# TeensyAmp_R5_1.net
KiCad netlist of a schematic drawn in EAGLE
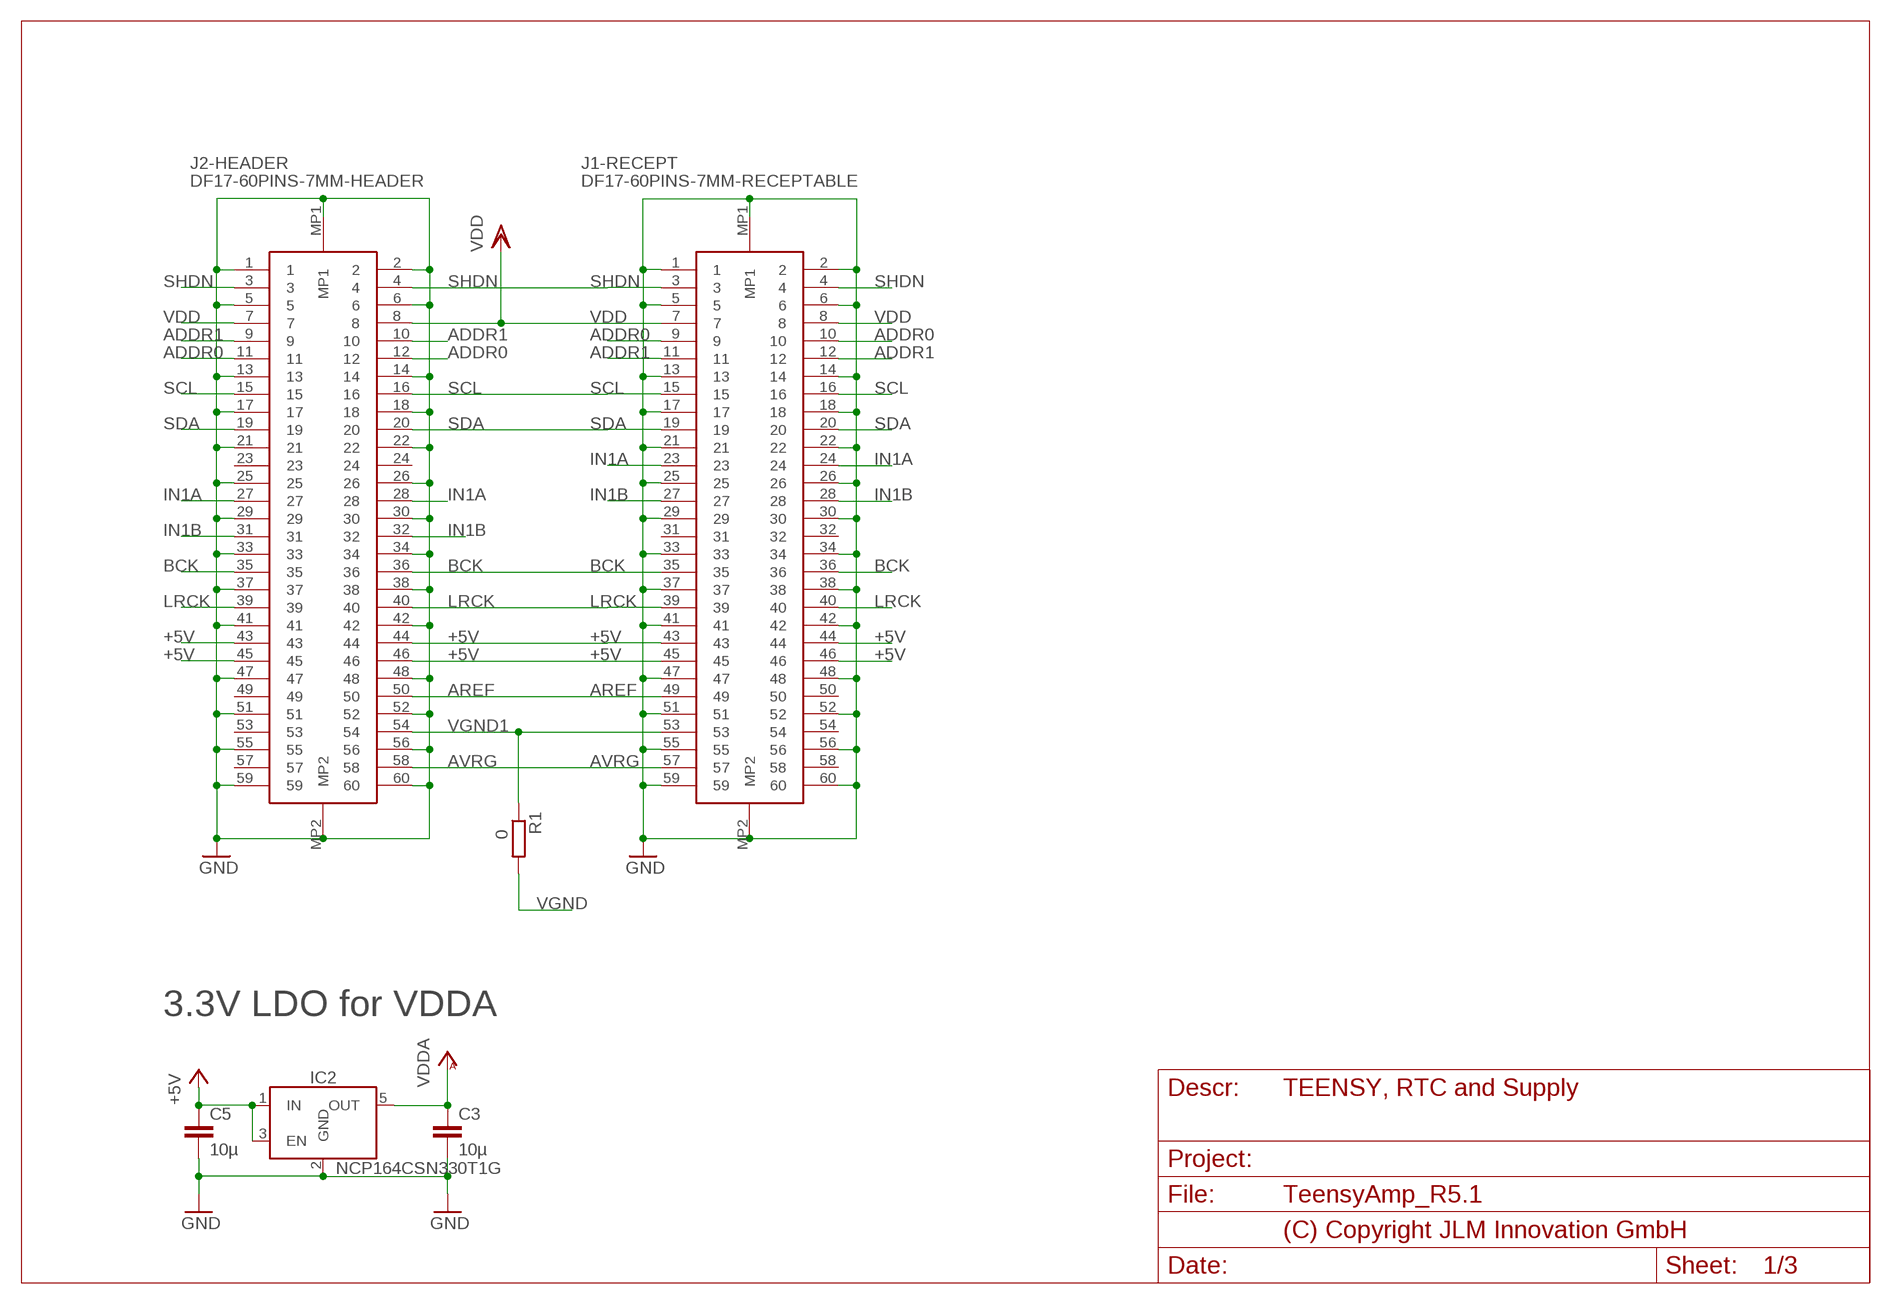
[diagram p0: schematic, sheet 1]
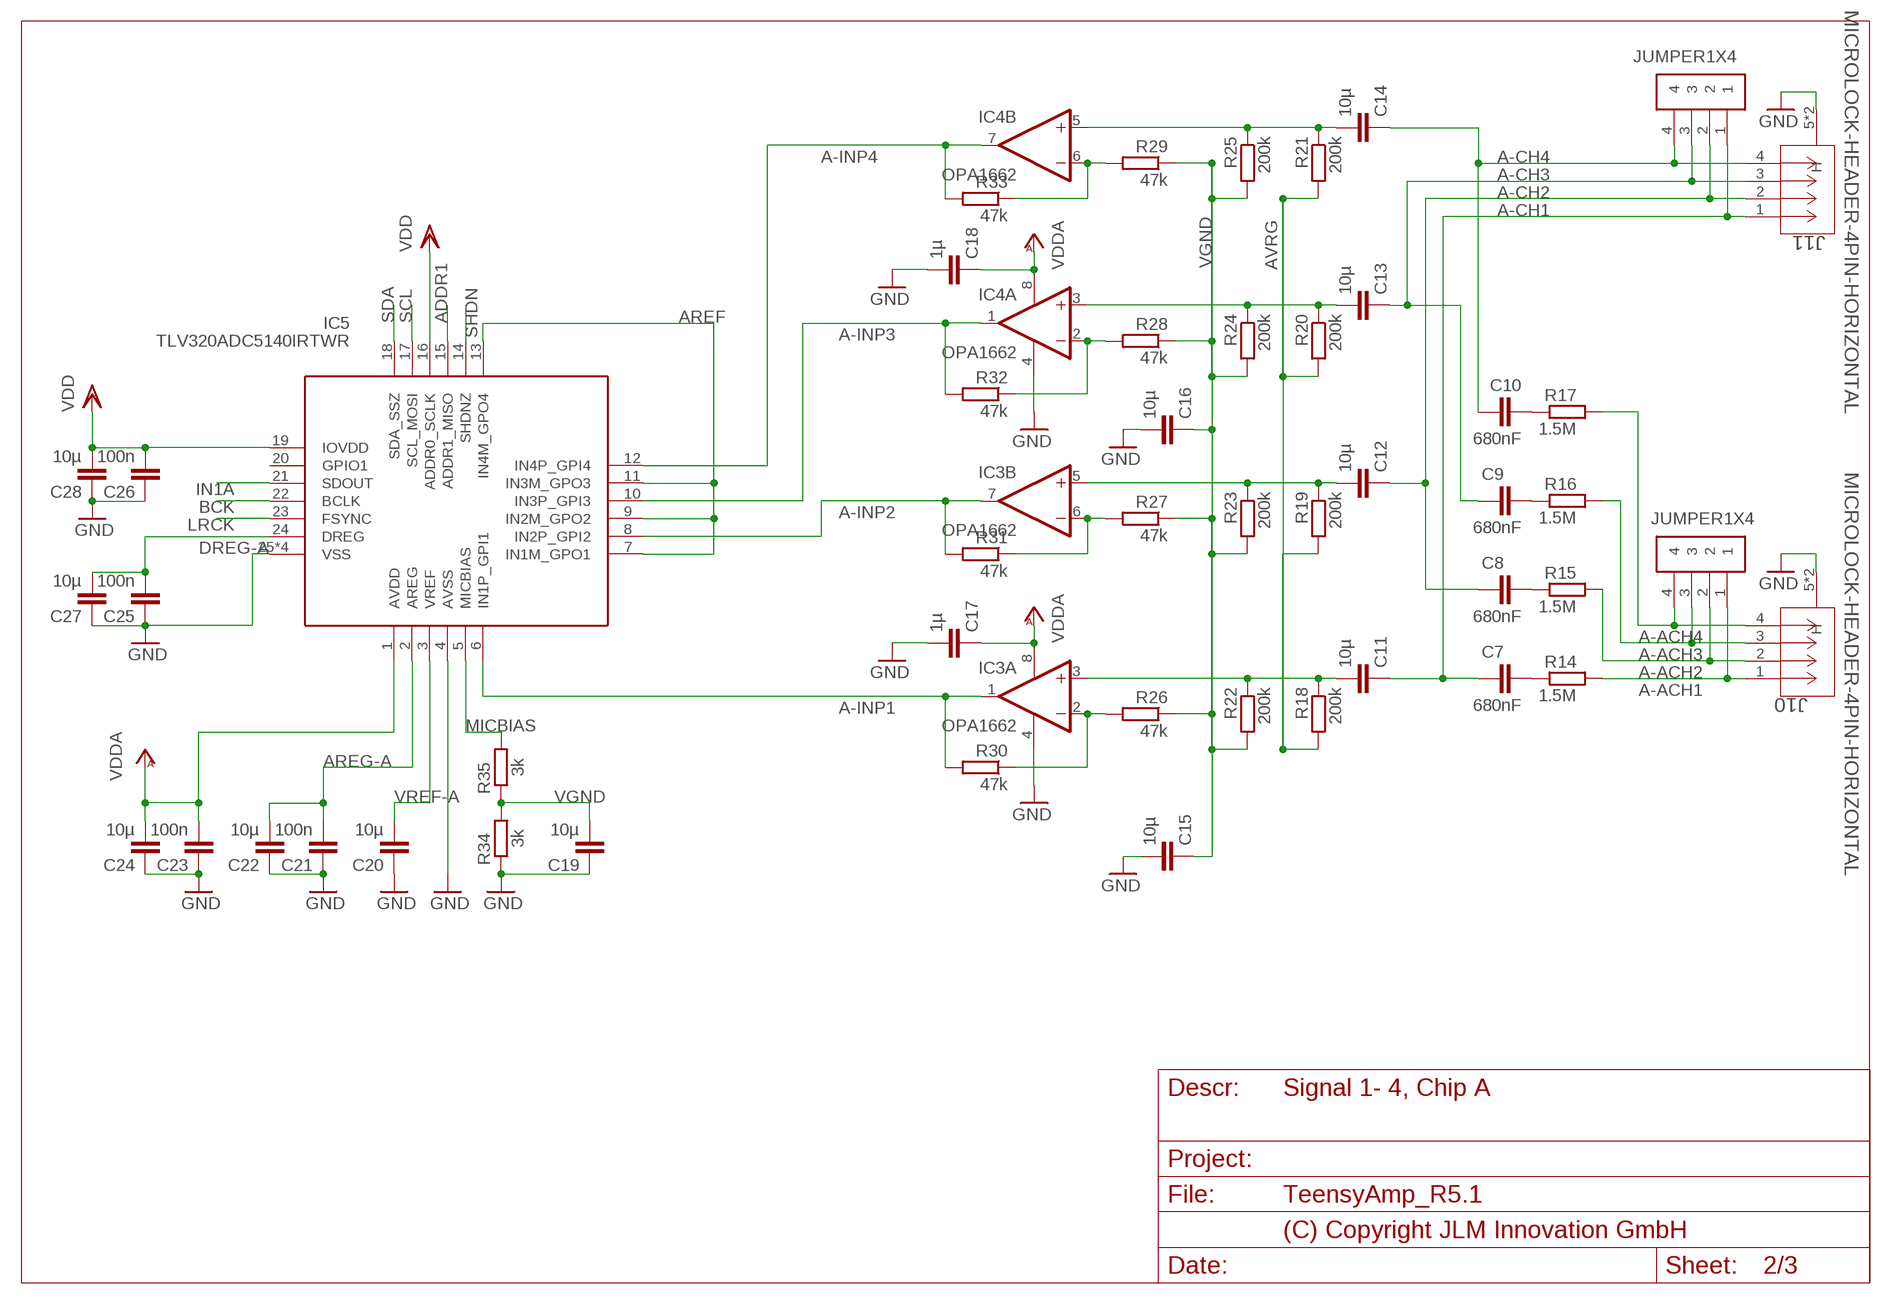
[diagram p1: schematic, sheet 2]
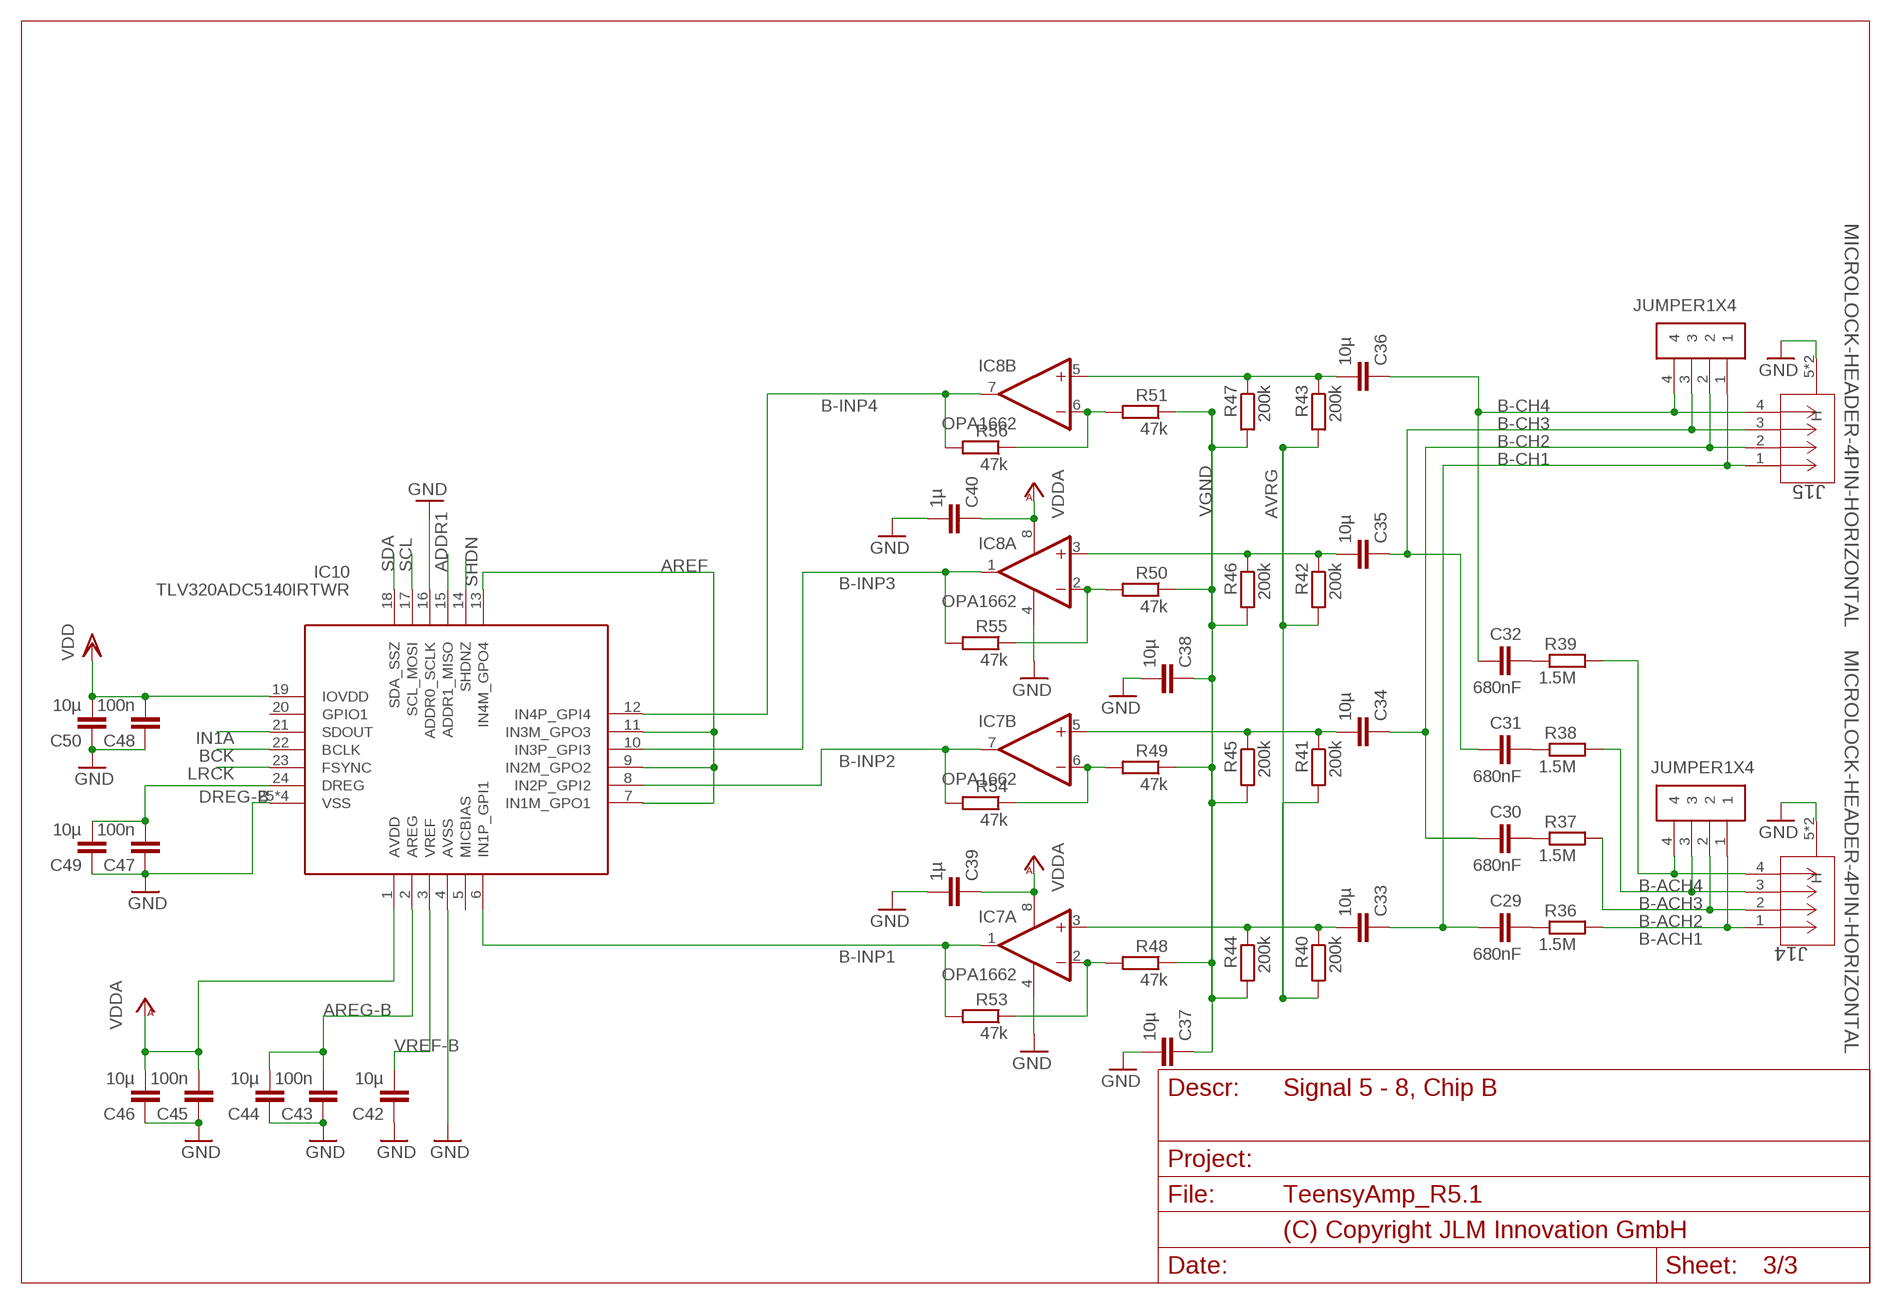
[diagram p2: schematic, sheet 3]

(export (version "E")
  (design (tool "Eeschema 10.0.6"))
  (components
    (comp (ref "C29")
      (value "680nF")
      (footprint "eagle-import:C0805")
      (libsource (lib "eagle-import") (part "C-EUC0805"))
    )
    (comp (ref "C30")
      (value "680nF")
      (footprint "eagle-import:C0805")
      (libsource (lib "eagle-import") (part "C-EUC0805"))
    )
    (comp (ref "C31")
      (value "680nF")
      (footprint "eagle-import:C0805")
      (libsource (lib "eagle-import") (part "C-EUC0805"))
    )
    (comp (ref "C32")
      (value "680nF")
      (footprint "eagle-import:C0805")
      (libsource (lib "eagle-import") (part "C-EUC0805"))
    )
    (comp (ref "C33")
      (value "10µ")
      (footprint "eagle-import:C0805")
      (libsource (lib "eagle-import") (part "C-EUC0805"))
    )
    (comp (ref "C34")
      (value "10µ")
      (footprint "eagle-import:C0805")
      (libsource (lib "eagle-import") (part "C-EUC0805"))
    )
    (comp (ref "C35")
      (value "10µ")
      (footprint "eagle-import:C0805")
      (libsource (lib "eagle-import") (part "C-EUC0805"))
    )
    (comp (ref "C36")
      (value "10µ")
      (footprint "eagle-import:C0805")
      (libsource (lib "eagle-import") (part "C-EUC0805"))
    )
    (comp (ref "C37")
      (value "10µ")
      (footprint "eagle-import:C0603")
      (libsource (lib "eagle-import") (part "C-EUC0603"))
    )
    (comp (ref "C38")
      (value "10µ")
      (footprint "eagle-import:C0603")
      (libsource (lib "eagle-import") (part "C-EUC0603"))
    )
    (comp (ref "C39")
      (value "1µ")
      (footprint "eagle-import:C0603")
      (libsource (lib "eagle-import") (part "C-EUC0603"))
    )
    (comp (ref "C40")
      (value "1µ")
      (footprint "eagle-import:C0603")
      (libsource (lib "eagle-import") (part "C-EUC0603"))
    )
    (comp (ref "C42")
      (value "10µ")
      (footprint "eagle-import:C0603")
      (libsource (lib "eagle-import") (part "C-EUC0603"))
    )
    (comp (ref "C43")
      (value "100n")
      (footprint "eagle-import:C0603")
      (libsource (lib "eagle-import") (part "C-EUC0603"))
    )
    (comp (ref "C44")
      (value "10µ")
      (footprint "eagle-import:C0603")
      (libsource (lib "eagle-import") (part "C-EUC0603"))
    )
    (comp (ref "C45")
      (value "100n")
      (footprint "eagle-import:C0603")
      (libsource (lib "eagle-import") (part "C-EUC0603"))
    )
    (comp (ref "C46")
      (value "10µ")
      (footprint "eagle-import:C0603")
      (libsource (lib "eagle-import") (part "C-EUC0603"))
    )
    (comp (ref "C47")
      (value "100n")
      (footprint "eagle-import:C0603")
      (libsource (lib "eagle-import") (part "C-EUC0603"))
    )
    (comp (ref "C48")
      (value "100n")
      (footprint "eagle-import:C0603")
      (libsource (lib "eagle-import") (part "C-EUC0603"))
    )
    (comp (ref "C49")
      (value "10µ")
      (footprint "eagle-import:C0603")
      (libsource (lib "eagle-import") (part "C-EUC0603"))
    )
    (comp (ref "C50")
      (value "10µ")
      (footprint "eagle-import:C0603")
      (libsource (lib "eagle-import") (part "C-EUC0603"))
    )
    (comp (ref "IC7")
      (value "OPA1662")
      (footprint "eagle-import:MSOP08")
      (libsource (lib "eagle-import") (part "OPA2E344"))
    )
    (comp (ref "IC8")
      (value "OPA1662")
      (footprint "eagle-import:MSOP08")
      (libsource (lib "eagle-import") (part "OPA2E344"))
    )
    (comp (ref "IC10")
      (value "TLV320ADC5140IRTWR")
      (footprint "eagle-import:QFN50P400X400X80-25N")
      (fields (field (name "MOUSER_PART_NUMBER") "595-V320ADC5140IRTWR"))
      (libsource (lib "eagle-import") (part "TLV320ADC5140IRTWR"))
    )
    (comp (ref "J14")
      (value "MICROLOCK-HEADER-4PIN-HORIZONTAL")
      (footprint "eagle-import:CONN04_5055670471_MOL")
      (fields
        (field (name "MANUFACTURER_PART_NUMBER") "5055670471")
        (field (name "COPYRIGHT") "Copyright (C) 2025 Ultra Librarian. All rights reserved.")
      )
      (libsource (lib "eagle-import") (part "MICROLOCK-HEADER-4PIN-HORIZONTAL"))
    )
    (comp (ref "J15")
      (value "MICROLOCK-HEADER-4PIN-HORIZONTAL")
      (footprint "eagle-import:CONN04_5055670471_MOL")
      (fields
        (field (name "MANUFACTURER_PART_NUMBER") "5055670471")
        (field (name "COPYRIGHT") "Copyright (C) 2025 Ultra Librarian. All rights reserved.")
      )
      (libsource (lib "eagle-import") (part "MICROLOCK-HEADER-4PIN-HORIZONTAL"))
    )
    (comp (ref "J16")
      (value "JUMPER1X4")
      (footprint "eagle-import:JMP1X4")
      (libsource (lib "eagle-import") (part "JUMPER1X4"))
    )
    (comp (ref "J17")
      (value "JUMPER1X4")
      (footprint "eagle-import:JMP1X4")
      (libsource (lib "eagle-import") (part "JUMPER1X4"))
    )
    (comp (ref "R36")
      (value "1.5M")
      (footprint "eagle-import:R0603")
      (libsource (lib "eagle-import") (part "R_JLMR0603"))
    )
    (comp (ref "R37")
      (value "1.5M")
      (footprint "eagle-import:R0603")
      (libsource (lib "eagle-import") (part "R_JLMR0603"))
    )
    (comp (ref "R38")
      (value "1.5M")
      (footprint "eagle-import:R0603")
      (libsource (lib "eagle-import") (part "R_JLMR0603"))
    )
    (comp (ref "R39")
      (value "1.5M")
      (footprint "eagle-import:R0603")
      (libsource (lib "eagle-import") (part "R_JLMR0603"))
    )
    (comp (ref "R40")
      (value "200k")
      (footprint "eagle-import:R0603")
      (libsource (lib "eagle-import") (part "R_JLMR0603"))
    )
    (comp (ref "R41")
      (value "200k")
      (footprint "eagle-import:R0603")
      (libsource (lib "eagle-import") (part "R_JLMR0603"))
    )
    (comp (ref "R42")
      (value "200k")
      (footprint "eagle-import:R0603")
      (libsource (lib "eagle-import") (part "R_JLMR0603"))
    )
    (comp (ref "R43")
      (value "200k")
      (footprint "eagle-import:R0603")
      (libsource (lib "eagle-import") (part "R_JLMR0603"))
    )
    (comp (ref "R44")
      (value "200k")
      (footprint "eagle-import:R0603")
      (libsource (lib "eagle-import") (part "R_JLMR0603"))
    )
    (comp (ref "R45")
      (value "200k")
      (footprint "eagle-import:R0603")
      (libsource (lib "eagle-import") (part "R_JLMR0603"))
    )
    (comp (ref "R46")
      (value "200k")
      (footprint "eagle-import:R0603")
      (libsource (lib "eagle-import") (part "R_JLMR0603"))
    )
    (comp (ref "R47")
      (value "200k")
      (footprint "eagle-import:R0603")
      (libsource (lib "eagle-import") (part "R_JLMR0603"))
    )
    (comp (ref "R48")
      (value "47k")
      (footprint "eagle-import:R0603")
      (libsource (lib "eagle-import") (part "R_JLMR0603"))
    )
    (comp (ref "R49")
      (value "47k")
      (footprint "eagle-import:R0603")
      (libsource (lib "eagle-import") (part "R_JLMR0603"))
    )
    (comp (ref "R50")
      (value "47k")
      (footprint "eagle-import:R0603")
      (libsource (lib "eagle-import") (part "R_JLMR0603"))
    )
    (comp (ref "R51")
      (value "47k")
      (footprint "eagle-import:R0603")
      (libsource (lib "eagle-import") (part "R_JLMR0603"))
    )
    (comp (ref "R53")
      (value "47k")
      (footprint "eagle-import:R0603")
      (libsource (lib "eagle-import") (part "R_JLMR0603"))
    )
    (comp (ref "R54")
      (value "47k")
      (footprint "eagle-import:R0603")
      (libsource (lib "eagle-import") (part "R_JLMR0603"))
    )
    (comp (ref "R55")
      (value "47k")
      (footprint "eagle-import:R0603")
      (libsource (lib "eagle-import") (part "R_JLMR0603"))
    )
    (comp (ref "R56")
      (value "47k")
      (footprint "eagle-import:R0603")
      (libsource (lib "eagle-import") (part "R_JLMR0603"))
    )
    (comp (ref "C3")
      (value "10µ")
      (footprint "eagle-import:C0603")
      (libsource (lib "eagle-import") (part "C-EUC0603"))
    )
    (comp (ref "C5")
      (value "10µ")
      (footprint "eagle-import:C0603")
      (libsource (lib "eagle-import") (part "C-EUC0603"))
    )
    (comp (ref "IC2")
      (value "NCP164CSN330T1G")
      (footprint "eagle-import:SOT23-5")
      (libsource (lib "eagle-import") (part "LDO_ENSOT23-5"))
    )
    (comp (ref "J1-RECEPT")
      (value "DF17-60PINS-7MM-RECEPTABLE")
      (footprint "eagle-import:DF173060DS05V57")
      (fields
        (field (name "MANUFACTURER_PART_NUMBER") "DF17(3.0)-60DS-0.5V(57)")
        (field (name "MOUSER_PART_NUMBER") "798-DF173060DS05V57")
      )
      (libsource (lib "eagle-import") (part "DF17-60PINS-7MM-RECEPTABLE"))
    )
    (comp (ref "J2-HEADER")
      (value "DF17-60PINS-7MM-HEADER")
      (footprint "eagle-import:DF174060DP05V57")
      (fields
        (field (name "MANUFACTURER_PART_NUMBER") "DF17(4.0)-60DP-0.5V(57)")
        (field (name "MOUSER_PART_NUMBER") "798-DF174060DP05V57")
      )
      (libsource (lib "eagle-import") (part "DF17-60PINS-7MM-HEADER"))
    )
    (comp (ref "R1")
      (value "0")
      (footprint "eagle-import:R0603")
      (libsource (lib "eagle-import") (part "R_JLMR0603"))
    )
    (comp (ref "C7")
      (value "680nF")
      (footprint "eagle-import:C0805")
      (libsource (lib "eagle-import") (part "C-EUC0805"))
    )
    (comp (ref "C8")
      (value "680nF")
      (footprint "eagle-import:C0805")
      (libsource (lib "eagle-import") (part "C-EUC0805"))
    )
    (comp (ref "C9")
      (value "680nF")
      (footprint "eagle-import:C0805")
      (libsource (lib "eagle-import") (part "C-EUC0805"))
    )
    (comp (ref "C10")
      (value "680nF")
      (footprint "eagle-import:C0805")
      (libsource (lib "eagle-import") (part "C-EUC0805"))
    )
    (comp (ref "C11")
      (value "10µ")
      (footprint "eagle-import:C0805")
      (libsource (lib "eagle-import") (part "C-EUC0805"))
    )
    (comp (ref "C12")
      (value "10µ")
      (footprint "eagle-import:C0805")
      (libsource (lib "eagle-import") (part "C-EUC0805"))
    )
    (comp (ref "C13")
      (value "10µ")
      (footprint "eagle-import:C0805")
      (libsource (lib "eagle-import") (part "C-EUC0805"))
    )
    (comp (ref "C14")
      (value "10µ")
      (footprint "eagle-import:C0805")
      (libsource (lib "eagle-import") (part "C-EUC0805"))
    )
    (comp (ref "C15")
      (value "10µ")
      (footprint "eagle-import:C0603")
      (libsource (lib "eagle-import") (part "C-EUC0603"))
    )
    (comp (ref "C16")
      (value "10µ")
      (footprint "eagle-import:C0603")
      (libsource (lib "eagle-import") (part "C-EUC0603"))
    )
    (comp (ref "C17")
      (value "1µ")
      (footprint "eagle-import:C0603")
      (libsource (lib "eagle-import") (part "C-EUC0603"))
    )
    (comp (ref "C18")
      (value "1µ")
      (footprint "eagle-import:C0603")
      (libsource (lib "eagle-import") (part "C-EUC0603"))
    )
    (comp (ref "C19")
      (value "10µ")
      (footprint "eagle-import:C0603")
      (libsource (lib "eagle-import") (part "C-EUC0603"))
    )
    (comp (ref "C20")
      (value "10µ")
      (footprint "eagle-import:C0603")
      (libsource (lib "eagle-import") (part "C-EUC0603"))
    )
    (comp (ref "C21")
      (value "100n")
      (footprint "eagle-import:C0603")
      (libsource (lib "eagle-import") (part "C-EUC0603"))
    )
    (comp (ref "C22")
      (value "10µ")
      (footprint "eagle-import:C0603")
      (libsource (lib "eagle-import") (part "C-EUC0603"))
    )
    (comp (ref "C23")
      (value "100n")
      (footprint "eagle-import:C0603")
      (libsource (lib "eagle-import") (part "C-EUC0603"))
    )
    (comp (ref "C24")
      (value "10µ")
      (footprint "eagle-import:C0603")
      (libsource (lib "eagle-import") (part "C-EUC0603"))
    )
    (comp (ref "C25")
      (value "100n")
      (footprint "eagle-import:C0603")
      (libsource (lib "eagle-import") (part "C-EUC0603"))
    )
    (comp (ref "C26")
      (value "100n")
      (footprint "eagle-import:C0603")
      (libsource (lib "eagle-import") (part "C-EUC0603"))
    )
    (comp (ref "C27")
      (value "10µ")
      (footprint "eagle-import:C0603")
      (libsource (lib "eagle-import") (part "C-EUC0603"))
    )
    (comp (ref "C28")
      (value "10µ")
      (footprint "eagle-import:C0603")
      (libsource (lib "eagle-import") (part "C-EUC0603"))
    )
    (comp (ref "IC3")
      (value "OPA1662")
      (footprint "eagle-import:MSOP08")
      (libsource (lib "eagle-import") (part "OPA2E344"))
    )
    (comp (ref "IC4")
      (value "OPA1662")
      (footprint "eagle-import:MSOP08")
      (libsource (lib "eagle-import") (part "OPA2E344"))
    )
    (comp (ref "IC5")
      (value "TLV320ADC5140IRTWR")
      (footprint "eagle-import:QFN50P400X400X80-25N")
      (fields (field (name "MOUSER_PART_NUMBER") "595-V320ADC5140IRTWR"))
      (libsource (lib "eagle-import") (part "TLV320ADC5140IRTWR"))
    )
    (comp (ref "J10")
      (value "MICROLOCK-HEADER-4PIN-HORIZONTAL")
      (footprint "eagle-import:CONN04_5055670471_MOL")
      (fields
        (field (name "MANUFACTURER_PART_NUMBER") "5055670471")
        (field (name "COPYRIGHT") "Copyright (C) 2025 Ultra Librarian. All rights reserved.")
      )
      (libsource (lib "eagle-import") (part "MICROLOCK-HEADER-4PIN-HORIZONTAL"))
    )
    (comp (ref "J11")
      (value "MICROLOCK-HEADER-4PIN-HORIZONTAL")
      (footprint "eagle-import:CONN04_5055670471_MOL")
      (fields
        (field (name "MANUFACTURER_PART_NUMBER") "5055670471")
        (field (name "COPYRIGHT") "Copyright (C) 2025 Ultra Librarian. All rights reserved.")
      )
      (libsource (lib "eagle-import") (part "MICROLOCK-HEADER-4PIN-HORIZONTAL"))
    )
    (comp (ref "J12")
      (value "JUMPER1X4")
      (footprint "eagle-import:JMP1X4")
      (libsource (lib "eagle-import") (part "JUMPER1X4"))
    )
    (comp (ref "J13")
      (value "JUMPER1X4")
      (footprint "eagle-import:JMP1X4")
      (libsource (lib "eagle-import") (part "JUMPER1X4"))
    )
    (comp (ref "R14")
      (value "1.5M")
      (footprint "eagle-import:R0603")
      (libsource (lib "eagle-import") (part "R_JLMR0603"))
    )
    (comp (ref "R15")
      (value "1.5M")
      (footprint "eagle-import:R0603")
      (libsource (lib "eagle-import") (part "R_JLMR0603"))
    )
    (comp (ref "R16")
      (value "1.5M")
      (footprint "eagle-import:R0603")
      (libsource (lib "eagle-import") (part "R_JLMR0603"))
    )
    (comp (ref "R17")
      (value "1.5M")
      (footprint "eagle-import:R0603")
      (libsource (lib "eagle-import") (part "R_JLMR0603"))
    )
    (comp (ref "R18")
      (value "200k")
      (footprint "eagle-import:R0603")
      (libsource (lib "eagle-import") (part "R_JLMR0603"))
    )
    (comp (ref "R19")
      (value "200k")
      (footprint "eagle-import:R0603")
      (libsource (lib "eagle-import") (part "R_JLMR0603"))
    )
    (comp (ref "R20")
      (value "200k")
      (footprint "eagle-import:R0603")
      (libsource (lib "eagle-import") (part "R_JLMR0603"))
    )
    (comp (ref "R21")
      (value "200k")
      (footprint "eagle-import:R0603")
      (libsource (lib "eagle-import") (part "R_JLMR0603"))
    )
    (comp (ref "R22")
      (value "200k")
      (footprint "eagle-import:R0603")
      (libsource (lib "eagle-import") (part "R_JLMR0603"))
    )
    (comp (ref "R23")
      (value "200k")
      (footprint "eagle-import:R0603")
      (libsource (lib "eagle-import") (part "R_JLMR0603"))
    )
    (comp (ref "R24")
      (value "200k")
      (footprint "eagle-import:R0603")
      (libsource (lib "eagle-import") (part "R_JLMR0603"))
    )
    (comp (ref "R25")
      (value "200k")
      (footprint "eagle-import:R0603")
      (libsource (lib "eagle-import") (part "R_JLMR0603"))
    )
    (comp (ref "R26")
      (value "47k")
      (footprint "eagle-import:R0603")
      (libsource (lib "eagle-import") (part "R_JLMR0603"))
    )
    (comp (ref "R27")
      (value "47k")
      (footprint "eagle-import:R0603")
      (libsource (lib "eagle-import") (part "R_JLMR0603"))
    )
    (comp (ref "R28")
      (value "47k")
      (footprint "eagle-import:R0603")
      (libsource (lib "eagle-import") (part "R_JLMR0603"))
    )
    (comp (ref "R29")
      (value "47k")
      (footprint "eagle-import:R0603")
      (libsource (lib "eagle-import") (part "R_JLMR0603"))
    )
    (comp (ref "R30")
      (value "47k")
      (footprint "eagle-import:R0603")
      (libsource (lib "eagle-import") (part "R_JLMR0603"))
    )
    (comp (ref "R31")
      (value "47k")
      (footprint "eagle-import:R0603")
      (libsource (lib "eagle-import") (part "R_JLMR0603"))
    )
    (comp (ref "R32")
      (value "47k")
      (footprint "eagle-import:R0603")
      (libsource (lib "eagle-import") (part "R_JLMR0603"))
    )
    (comp (ref "R33")
      (value "47k")
      (footprint "eagle-import:R0603")
      (libsource (lib "eagle-import") (part "R_JLMR0603"))
    )
    (comp (ref "R34")
      (value "3k")
      (footprint "eagle-import:R0603")
      (libsource (lib "eagle-import") (part "R_JLMR0603"))
    )
    (comp (ref "R35")
      (value "3k")
      (footprint "eagle-import:R0603")
      (libsource (lib "eagle-import") (part "R_JLMR0603"))
    )
  )
  (nets
    (net (code "1") (name "+5V") (class "Default")
      (node (ref "C5") (pin "1") (pinfunction "1_1") (pintype "passive"))
      (node (ref "IC2") (pin "1") (pinfunction "IN_1") (pintype "input"))
      (node (ref "IC2") (pin "3") (pinfunction "EN_3") (pintype "input"))
      (node (ref "J1-RECEPT") (pin "43") (pinfunction "43_43") (pintype "bidirectional"))
      (node (ref "J1-RECEPT") (pin "44") (pinfunction "44_44") (pintype "bidirectional"))
      (node (ref "J1-RECEPT") (pin "45") (pinfunction "45_45") (pintype "bidirectional"))
      (node (ref "J1-RECEPT") (pin "46") (pinfunction "46_46") (pintype "bidirectional"))
      (node (ref "J2-HEADER") (pin "43") (pinfunction "43_43") (pintype "bidirectional"))
      (node (ref "J2-HEADER") (pin "44") (pinfunction "44_44") (pintype "bidirectional"))
      (node (ref "J2-HEADER") (pin "45") (pinfunction "45_45") (pintype "bidirectional"))
      (node (ref "J2-HEADER") (pin "46") (pinfunction "46_46") (pintype "bidirectional"))
    )
    (net (code "2") (name "A-ACH1") (class "Default")
      (node (ref "J10") (pin "1") (pinfunction "1_1") (pintype "passive"))
      (node (ref "J12") (pin "1") (pinfunction "1_1") (pintype "bidirectional"))
      (node (ref "R14") (pin "1") (pinfunction "1_1") (pintype "passive"))
    )
    (net (code "3") (name "A-ACH2") (class "Default")
      (node (ref "J10") (pin "2") (pinfunction "2_2") (pintype "passive"))
      (node (ref "J12") (pin "2") (pinfunction "2_2") (pintype "bidirectional"))
      (node (ref "R15") (pin "1") (pinfunction "1_1") (pintype "passive"))
    )
    (net (code "4") (name "A-ACH3") (class "Default")
      (node (ref "J10") (pin "3") (pinfunction "3_3") (pintype "passive"))
      (node (ref "J12") (pin "3") (pinfunction "3_3") (pintype "bidirectional"))
      (node (ref "R16") (pin "1") (pinfunction "1_1") (pintype "passive"))
    )
    (net (code "5") (name "A-ACH4") (class "Default")
      (node (ref "J10") (pin "4") (pinfunction "4_4") (pintype "passive"))
      (node (ref "J12") (pin "4") (pinfunction "4_4") (pintype "bidirectional"))
      (node (ref "R17") (pin "1") (pinfunction "1_1") (pintype "passive"))
    )
    (net (code "6") (name "A-CH1") (class "Default")
      (node (ref "C11") (pin "1") (pinfunction "1_1") (pintype "passive"))
      (node (ref "C7") (pin "2") (pinfunction "2_2") (pintype "passive"))
      (node (ref "J11") (pin "1") (pinfunction "1_1") (pintype "passive"))
      (node (ref "J13") (pin "1") (pinfunction "1_1") (pintype "bidirectional"))
    )
    (net (code "7") (name "A-CH2") (class "Default")
      (node (ref "C12") (pin "1") (pinfunction "1_1") (pintype "passive"))
      (node (ref "C8") (pin "2") (pinfunction "2_2") (pintype "passive"))
      (node (ref "J11") (pin "2") (pinfunction "2_2") (pintype "passive"))
      (node (ref "J13") (pin "2") (pinfunction "2_2") (pintype "bidirectional"))
    )
    (net (code "8") (name "A-CH3") (class "Default")
      (node (ref "C13") (pin "1") (pinfunction "1_1") (pintype "passive"))
      (node (ref "C9") (pin "2") (pinfunction "2_2") (pintype "passive"))
      (node (ref "J11") (pin "3") (pinfunction "3_3") (pintype "passive"))
      (node (ref "J13") (pin "3") (pinfunction "3_3") (pintype "bidirectional"))
    )
    (net (code "9") (name "A-CH4") (class "Default")
      (node (ref "C10") (pin "2") (pinfunction "2_2") (pintype "passive"))
      (node (ref "C14") (pin "1") (pinfunction "1_1") (pintype "passive"))
      (node (ref "J11") (pin "4") (pinfunction "4_4") (pintype "passive"))
      (node (ref "J13") (pin "4") (pinfunction "4_4") (pintype "bidirectional"))
    )
    (net (code "10") (name "A-INP1") (class "Default")
      (node (ref "IC3") (pin "1") (pinfunction "OUT_1") (pintype "output"))
      (node (ref "IC5") (pin "6") (pinfunction "IN1P_GPI1_6") (pintype "bidirectional"))
      (node (ref "R30") (pin "2") (pinfunction "2_2") (pintype "passive"))
    )
    (net (code "11") (name "A-INP2") (class "Default")
      (node (ref "IC3") (pin "7") (pinfunction "OUT_7") (pintype "output"))
      (node (ref "IC5") (pin "8") (pinfunction "IN2P_GPI2_8") (pintype "bidirectional"))
      (node (ref "R31") (pin "2") (pinfunction "2_2") (pintype "passive"))
    )
    (net (code "12") (name "A-INP3") (class "Default")
      (node (ref "IC4") (pin "1") (pinfunction "OUT_1") (pintype "output"))
      (node (ref "IC5") (pin "10") (pinfunction "IN3P_GPI3_10") (pintype "bidirectional"))
      (node (ref "R32") (pin "2") (pinfunction "2_2") (pintype "passive"))
    )
    (net (code "13") (name "A-INP4") (class "Default")
      (node (ref "IC4") (pin "7") (pinfunction "OUT_7") (pintype "output"))
      (node (ref "IC5") (pin "12") (pinfunction "IN4P_GPI4_12") (pintype "bidirectional"))
      (node (ref "R33") (pin "2") (pinfunction "2_2") (pintype "passive"))
    )
    (net (code "14") (name "ADDR0") (class "Default")
      (node (ref "J1-RECEPT") (pin "10") (pinfunction "10_10") (pintype "bidirectional"))
      (node (ref "J1-RECEPT") (pin "9") (pinfunction "9_9") (pintype "bidirectional"))
      (node (ref "J2-HEADER") (pin "11") (pinfunction "11_11") (pintype "bidirectional"))
      (node (ref "J2-HEADER") (pin "12") (pinfunction "12_12") (pintype "bidirectional"))
    )
    (net (code "15") (name "ADDR1") (class "Default")
      (node (ref "IC10") (pin "15") (pinfunction "ADDR1_MISO_15") (pintype "bidirectional"))
      (node (ref "IC5") (pin "15") (pinfunction "ADDR1_MISO_15") (pintype "bidirectional"))
      (node (ref "J1-RECEPT") (pin "11") (pinfunction "11_11") (pintype "bidirectional"))
      (node (ref "J1-RECEPT") (pin "12") (pinfunction "12_12") (pintype "bidirectional"))
      (node (ref "J2-HEADER") (pin "10") (pinfunction "10_10") (pintype "bidirectional"))
      (node (ref "J2-HEADER") (pin "9") (pinfunction "9_9") (pintype "bidirectional"))
    )
    (net (code "16") (name "AREF") (class "Default")
      (node (ref "IC10") (pin "11") (pinfunction "IN3M_GPO3_11") (pintype "bidirectional"))
      (node (ref "IC10") (pin "13") (pinfunction "IN4M_GPO4_13") (pintype "bidirectional"))
      (node (ref "IC10") (pin "7") (pinfunction "IN1M_GPO1_7") (pintype "bidirectional"))
      (node (ref "IC10") (pin "9") (pinfunction "IN2M_GPO2_9") (pintype "bidirectional"))
      (node (ref "IC5") (pin "11") (pinfunction "IN3M_GPO3_11") (pintype "bidirectional"))
      (node (ref "IC5") (pin "13") (pinfunction "IN4M_GPO4_13") (pintype "bidirectional"))
      (node (ref "IC5") (pin "7") (pinfunction "IN1M_GPO1_7") (pintype "bidirectional"))
      (node (ref "IC5") (pin "9") (pinfunction "IN2M_GPO2_9") (pintype "bidirectional"))
      (node (ref "J1-RECEPT") (pin "49") (pinfunction "49_49") (pintype "bidirectional"))
      (node (ref "J2-HEADER") (pin "50") (pinfunction "50_50") (pintype "bidirectional"))
    )
    (net (code "17") (name "AREG-A") (class "Default")
      (node (ref "C21") (pin "2") (pinfunction "2_2") (pintype "passive"))
      (node (ref "C22") (pin "2") (pinfunction "2_2") (pintype "passive"))
      (node (ref "IC5") (pin "2") (pinfunction "AREG_2") (pintype "bidirectional"))
    )
    (net (code "18") (name "AREG-B") (class "Default")
      (node (ref "C43") (pin "2") (pinfunction "2_2") (pintype "passive"))
      (node (ref "C44") (pin "2") (pinfunction "2_2") (pintype "passive"))
      (node (ref "IC10") (pin "2") (pinfunction "AREG_2") (pintype "bidirectional"))
    )
    (net (code "19") (name "AVRG") (class "Default")
      (node (ref "J1-RECEPT") (pin "57") (pinfunction "57_57") (pintype "bidirectional"))
      (node (ref "J2-HEADER") (pin "58") (pinfunction "58_58") (pintype "bidirectional"))
      (node (ref "R18") (pin "2") (pinfunction "2_2") (pintype "passive"))
      (node (ref "R19") (pin "2") (pinfunction "2_2") (pintype "passive"))
      (node (ref "R20") (pin "2") (pinfunction "2_2") (pintype "passive"))
      (node (ref "R21") (pin "2") (pinfunction "2_2") (pintype "passive"))
      (node (ref "R40") (pin "2") (pinfunction "2_2") (pintype "passive"))
      (node (ref "R41") (pin "2") (pinfunction "2_2") (pintype "passive"))
      (node (ref "R42") (pin "2") (pinfunction "2_2") (pintype "passive"))
      (node (ref "R43") (pin "2") (pinfunction "2_2") (pintype "passive"))
    )
    (net (code "20") (name "B-ACH1") (class "Default")
      (node (ref "J14") (pin "1") (pinfunction "1_1") (pintype "passive"))
      (node (ref "J16") (pin "1") (pinfunction "1_1") (pintype "bidirectional"))
      (node (ref "R36") (pin "1") (pinfunction "1_1") (pintype "passive"))
    )
    (net (code "21") (name "B-ACH2") (class "Default")
      (node (ref "J14") (pin "2") (pinfunction "2_2") (pintype "passive"))
      (node (ref "J16") (pin "2") (pinfunction "2_2") (pintype "bidirectional"))
      (node (ref "R37") (pin "1") (pinfunction "1_1") (pintype "passive"))
    )
    (net (code "22") (name "B-ACH3") (class "Default")
      (node (ref "J14") (pin "3") (pinfunction "3_3") (pintype "passive"))
      (node (ref "J16") (pin "3") (pinfunction "3_3") (pintype "bidirectional"))
      (node (ref "R38") (pin "1") (pinfunction "1_1") (pintype "passive"))
    )
    (net (code "23") (name "B-ACH4") (class "Default")
      (node (ref "J14") (pin "4") (pinfunction "4_4") (pintype "passive"))
      (node (ref "J16") (pin "4") (pinfunction "4_4") (pintype "bidirectional"))
      (node (ref "R39") (pin "1") (pinfunction "1_1") (pintype "passive"))
    )
    (net (code "24") (name "B-CH1") (class "Default")
      (node (ref "C29") (pin "2") (pinfunction "2_2") (pintype "passive"))
      (node (ref "C33") (pin "1") (pinfunction "1_1") (pintype "passive"))
      (node (ref "J15") (pin "1") (pinfunction "1_1") (pintype "passive"))
      (node (ref "J17") (pin "1") (pinfunction "1_1") (pintype "bidirectional"))
    )
    (net (code "25") (name "B-CH2") (class "Default")
      (node (ref "C30") (pin "2") (pinfunction "2_2") (pintype "passive"))
      (node (ref "C34") (pin "1") (pinfunction "1_1") (pintype "passive"))
      (node (ref "J15") (pin "2") (pinfunction "2_2") (pintype "passive"))
      (node (ref "J17") (pin "2") (pinfunction "2_2") (pintype "bidirectional"))
    )
    (net (code "26") (name "B-CH3") (class "Default")
      (node (ref "C31") (pin "2") (pinfunction "2_2") (pintype "passive"))
      (node (ref "C35") (pin "1") (pinfunction "1_1") (pintype "passive"))
      (node (ref "J15") (pin "3") (pinfunction "3_3") (pintype "passive"))
      (node (ref "J17") (pin "3") (pinfunction "3_3") (pintype "bidirectional"))
    )
    (net (code "27") (name "B-CH4") (class "Default")
      (node (ref "C32") (pin "2") (pinfunction "2_2") (pintype "passive"))
      (node (ref "C36") (pin "1") (pinfunction "1_1") (pintype "passive"))
      (node (ref "J15") (pin "4") (pinfunction "4_4") (pintype "passive"))
      (node (ref "J17") (pin "4") (pinfunction "4_4") (pintype "bidirectional"))
    )
    (net (code "28") (name "B-INP1") (class "Default")
      (node (ref "IC10") (pin "6") (pinfunction "IN1P_GPI1_6") (pintype "bidirectional"))
      (node (ref "IC7") (pin "1") (pinfunction "OUT_1") (pintype "output"))
      (node (ref "R53") (pin "2") (pinfunction "2_2") (pintype "passive"))
    )
    (net (code "29") (name "B-INP2") (class "Default")
      (node (ref "IC10") (pin "8") (pinfunction "IN2P_GPI2_8") (pintype "bidirectional"))
      (node (ref "IC7") (pin "7") (pinfunction "OUT_7") (pintype "output"))
      (node (ref "R54") (pin "2") (pinfunction "2_2") (pintype "passive"))
    )
    (net (code "30") (name "B-INP3") (class "Default")
      (node (ref "IC10") (pin "10") (pinfunction "IN3P_GPI3_10") (pintype "bidirectional"))
      (node (ref "IC8") (pin "1") (pinfunction "OUT_1") (pintype "output"))
      (node (ref "R55") (pin "2") (pinfunction "2_2") (pintype "passive"))
    )
    (net (code "31") (name "B-INP4") (class "Default")
      (node (ref "IC10") (pin "12") (pinfunction "IN4P_GPI4_12") (pintype "bidirectional"))
      (node (ref "IC8") (pin "7") (pinfunction "OUT_7") (pintype "output"))
      (node (ref "R56") (pin "2") (pinfunction "2_2") (pintype "passive"))
    )
    (net (code "32") (name "BCK") (class "Default")
      (node (ref "IC10") (pin "22") (pinfunction "BCLK_22") (pintype "bidirectional"))
      (node (ref "IC5") (pin "22") (pinfunction "BCLK_22") (pintype "bidirectional"))
      (node (ref "J1-RECEPT") (pin "35") (pinfunction "35_35") (pintype "bidirectional"))
      (node (ref "J1-RECEPT") (pin "36") (pinfunction "36_36") (pintype "bidirectional"))
      (node (ref "J2-HEADER") (pin "35") (pinfunction "35_35") (pintype "bidirectional"))
      (node (ref "J2-HEADER") (pin "36") (pinfunction "36_36") (pintype "bidirectional"))
    )
    (net (code "33") (name "DREG-A") (class "Default")
      (node (ref "C25") (pin "2") (pinfunction "2_2") (pintype "passive"))
      (node (ref "C27") (pin "2") (pinfunction "2_2") (pintype "passive"))
      (node (ref "IC5") (pin "24") (pinfunction "DREG_24") (pintype "bidirectional"))
    )
    (net (code "34") (name "DREG-B") (class "Default")
      (node (ref "C47") (pin "2") (pinfunction "2_2") (pintype "passive"))
      (node (ref "C49") (pin "2") (pinfunction "2_2") (pintype "passive"))
      (node (ref "IC10") (pin "24") (pinfunction "DREG_24") (pintype "bidirectional"))
    )
    (net (code "35") (name "GND") (class "Default")
      (node (ref "C15") (pin "2") (pinfunction "2_2") (pintype "passive"))
      (node (ref "C16") (pin "2") (pinfunction "2_2") (pintype "passive"))
      (node (ref "C17") (pin "2") (pinfunction "2_2") (pintype "passive"))
      (node (ref "C18") (pin "2") (pinfunction "2_2") (pintype "passive"))
      (node (ref "C19") (pin "1") (pinfunction "1_1") (pintype "passive"))
      (node (ref "C20") (pin "1") (pinfunction "1_1") (pintype "passive"))
      (node (ref "C21") (pin "1") (pinfunction "1_1") (pintype "passive"))
      (node (ref "C22") (pin "1") (pinfunction "1_1") (pintype "passive"))
      (node (ref "C23") (pin "1") (pinfunction "1_1") (pintype "passive"))
      (node (ref "C24") (pin "1") (pinfunction "1_1") (pintype "passive"))
      (node (ref "C25") (pin "1") (pinfunction "1_1") (pintype "passive"))
      (node (ref "C26") (pin "1") (pinfunction "1_1") (pintype "passive"))
      (node (ref "C27") (pin "1") (pinfunction "1_1") (pintype "passive"))
      (node (ref "C28") (pin "1") (pinfunction "1_1") (pintype "passive"))
      (node (ref "C3") (pin "2") (pinfunction "2_2") (pintype "passive"))
      (node (ref "C37") (pin "2") (pinfunction "2_2") (pintype "passive"))
      (node (ref "C38") (pin "2") (pinfunction "2_2") (pintype "passive"))
      (node (ref "C39") (pin "2") (pinfunction "2_2") (pintype "passive"))
      (node (ref "C40") (pin "2") (pinfunction "2_2") (pintype "passive"))
      (node (ref "C42") (pin "1") (pinfunction "1_1") (pintype "passive"))
      (node (ref "C43") (pin "1") (pinfunction "1_1") (pintype "passive"))
      (node (ref "C44") (pin "1") (pinfunction "1_1") (pintype "passive"))
      (node (ref "C45") (pin "1") (pinfunction "1_1") (pintype "passive"))
      (node (ref "C46") (pin "1") (pinfunction "1_1") (pintype "passive"))
      (node (ref "C47") (pin "1") (pinfunction "1_1") (pintype "passive"))
      (node (ref "C48") (pin "1") (pinfunction "1_1") (pintype "passive"))
      (node (ref "C49") (pin "1") (pinfunction "1_1") (pintype "passive"))
      (node (ref "C5") (pin "2") (pinfunction "2_2") (pintype "passive"))
      (node (ref "C50") (pin "1") (pinfunction "1_1") (pintype "passive"))
      (node (ref "IC10") (pin "16") (pinfunction "ADDR0_SCLK_16") (pintype "bidirectional"))
      (node (ref "IC10") (pin "25") (pinfunction "VSS_25") (pintype "bidirectional"))
      (node (ref "IC10") (pin "26") (pinfunction "VSS_26") (pintype "bidirectional"))
      (node (ref "IC10") (pin "27") (pinfunction "VSS_27") (pintype "bidirectional"))
      (node (ref "IC10") (pin "28") (pinfunction "VSS_28") (pintype "bidirectional"))
      (node (ref "IC10") (pin "4") (pinfunction "AVSS_4") (pintype "bidirectional"))
      (node (ref "IC2") (pin "2") (pinfunction "GND_2") (pintype "power_in"))
      (node (ref "IC3") (pin "4") (pinfunction "V-_4") (pintype "power_in"))
      (node (ref "IC4") (pin "4") (pinfunction "V-_4") (pintype "power_in"))
      (node (ref "IC5") (pin "25") (pinfunction "VSS_25") (pintype "bidirectional"))
      (node (ref "IC5") (pin "26") (pinfunction "VSS_26") (pintype "bidirectional"))
      (node (ref "IC5") (pin "27") (pinfunction "VSS_27") (pintype "bidirectional"))
      (node (ref "IC5") (pin "28") (pinfunction "VSS_28") (pintype "bidirectional"))
      (node (ref "IC5") (pin "4") (pinfunction "AVSS_4") (pintype "bidirectional"))
      (node (ref "IC7") (pin "4") (pinfunction "V-_4") (pintype "power_in"))
      (node (ref "IC8") (pin "4") (pinfunction "V-_4") (pintype "power_in"))
      (node (ref "J1-RECEPT") (pin "1") (pinfunction "1_1") (pintype "bidirectional"))
      (node (ref "J1-RECEPT") (pin "13") (pinfunction "13_13") (pintype "bidirectional"))
      (node (ref "J1-RECEPT") (pin "14") (pinfunction "14_14") (pintype "bidirectional"))
      (node (ref "J1-RECEPT") (pin "17") (pinfunction "17_17") (pintype "bidirectional"))
      (node (ref "J1-RECEPT") (pin "18") (pinfunction "18_18") (pintype "bidirectional"))
      (node (ref "J1-RECEPT") (pin "2") (pinfunction "2_2") (pintype "bidirectional"))
      (node (ref "J1-RECEPT") (pin "21") (pinfunction "21_21") (pintype "bidirectional"))
      (node (ref "J1-RECEPT") (pin "22") (pinfunction "22_22") (pintype "bidirectional"))
      (node (ref "J1-RECEPT") (pin "25") (pinfunction "25_25") (pintype "bidirectional"))
      (node (ref "J1-RECEPT") (pin "26") (pinfunction "26_26") (pintype "bidirectional"))
      (node (ref "J1-RECEPT") (pin "29") (pinfunction "29_29") (pintype "bidirectional"))
      (node (ref "J1-RECEPT") (pin "30") (pinfunction "30_30") (pintype "bidirectional"))
      (node (ref "J1-RECEPT") (pin "33") (pinfunction "33_33") (pintype "bidirectional"))
      (node (ref "J1-RECEPT") (pin "34") (pinfunction "34_34") (pintype "bidirectional"))
      (node (ref "J1-RECEPT") (pin "37") (pinfunction "37_37") (pintype "bidirectional"))
      (node (ref "J1-RECEPT") (pin "38") (pinfunction "38_38") (pintype "bidirectional"))
      (node (ref "J1-RECEPT") (pin "41") (pinfunction "41_41") (pintype "bidirectional"))
      (node (ref "J1-RECEPT") (pin "42") (pinfunction "42_42") (pintype "bidirectional"))
      (node (ref "J1-RECEPT") (pin "47") (pinfunction "47_47") (pintype "bidirectional"))
      (node (ref "J1-RECEPT") (pin "48") (pinfunction "48_48") (pintype "bidirectional"))
      (node (ref "J1-RECEPT") (pin "5") (pinfunction "5_5") (pintype "bidirectional"))
      (node (ref "J1-RECEPT") (pin "51") (pinfunction "51_51") (pintype "bidirectional"))
      (node (ref "J1-RECEPT") (pin "52") (pinfunction "52_52") (pintype "bidirectional"))
      (node (ref "J1-RECEPT") (pin "55") (pinfunction "55_55") (pintype "bidirectional"))
      (node (ref "J1-RECEPT") (pin "56") (pinfunction "56_56") (pintype "bidirectional"))
      (node (ref "J1-RECEPT") (pin "59") (pinfunction "59_59") (pintype "bidirectional"))
      (node (ref "J1-RECEPT") (pin "6") (pinfunction "6_6") (pintype "bidirectional"))
      (node (ref "J1-RECEPT") (pin "60") (pinfunction "60_60") (pintype "bidirectional"))
      (node (ref "J1-RECEPT") (pin "MP1") (pinfunction "MP1_MP1") (pintype "bidirectional"))
      (node (ref "J1-RECEPT") (pin "MP2") (pinfunction "MP2_MP2") (pintype "bidirectional"))
      (node (ref "J10") (pin "5") (pinfunction "H_5") (pintype "passive"))
      (node (ref "J10") (pin "6") (pinfunction "H_6") (pintype "passive"))
      (node (ref "J11") (pin "5") (pinfunction "H_5") (pintype "passive"))
      (node (ref "J11") (pin "6") (pinfunction "H_6") (pintype "passive"))
      (node (ref "J14") (pin "5") (pinfunction "H_5") (pintype "passive"))
      (node (ref "J14") (pin "6") (pinfunction "H_6") (pintype "passive"))
      (node (ref "J15") (pin "5") (pinfunction "H_5") (pintype "passive"))
      (node (ref "J15") (pin "6") (pinfunction "H_6") (pintype "passive"))
      (node (ref "J2-HEADER") (pin "1") (pinfunction "1_1") (pintype "bidirectional"))
      (node (ref "J2-HEADER") (pin "13") (pinfunction "13_13") (pintype "bidirectional"))
      (node (ref "J2-HEADER") (pin "14") (pinfunction "14_14") (pintype "bidirectional"))
      (node (ref "J2-HEADER") (pin "17") (pinfunction "17_17") (pintype "bidirectional"))
      (node (ref "J2-HEADER") (pin "18") (pinfunction "18_18") (pintype "bidirectional"))
      (node (ref "J2-HEADER") (pin "2") (pinfunction "2_2") (pintype "bidirectional"))
      (node (ref "J2-HEADER") (pin "21") (pinfunction "21_21") (pintype "bidirectional"))
      (node (ref "J2-HEADER") (pin "22") (pinfunction "22_22") (pintype "bidirectional"))
      (node (ref "J2-HEADER") (pin "25") (pinfunction "25_25") (pintype "bidirectional"))
      (node (ref "J2-HEADER") (pin "26") (pinfunction "26_26") (pintype "bidirectional"))
      (node (ref "J2-HEADER") (pin "29") (pinfunction "29_29") (pintype "bidirectional"))
      (node (ref "J2-HEADER") (pin "30") (pinfunction "30_30") (pintype "bidirectional"))
      (node (ref "J2-HEADER") (pin "33") (pinfunction "33_33") (pintype "bidirectional"))
      (node (ref "J2-HEADER") (pin "34") (pinfunction "34_34") (pintype "bidirectional"))
      (node (ref "J2-HEADER") (pin "37") (pinfunction "37_37") (pintype "bidirectional"))
      (node (ref "J2-HEADER") (pin "38") (pinfunction "38_38") (pintype "bidirectional"))
      (node (ref "J2-HEADER") (pin "41") (pinfunction "41_41") (pintype "bidirectional"))
      (node (ref "J2-HEADER") (pin "42") (pinfunction "42_42") (pintype "bidirectional"))
      (node (ref "J2-HEADER") (pin "47") (pinfunction "47_47") (pintype "bidirectional"))
      (node (ref "J2-HEADER") (pin "48") (pinfunction "48_48") (pintype "bidirectional"))
      (node (ref "J2-HEADER") (pin "5") (pinfunction "5_5") (pintype "bidirectional"))
      (node (ref "J2-HEADER") (pin "51") (pinfunction "51_51") (pintype "bidirectional"))
      (node (ref "J2-HEADER") (pin "52") (pinfunction "52_52") (pintype "bidirectional"))
      (node (ref "J2-HEADER") (pin "55") (pinfunction "55_55") (pintype "bidirectional"))
      (node (ref "J2-HEADER") (pin "56") (pinfunction "56_56") (pintype "bidirectional"))
      (node (ref "J2-HEADER") (pin "59") (pinfunction "59_59") (pintype "bidirectional"))
      (node (ref "J2-HEADER") (pin "6") (pinfunction "6_6") (pintype "bidirectional"))
      (node (ref "J2-HEADER") (pin "60") (pinfunction "60_60") (pintype "bidirectional"))
      (node (ref "J2-HEADER") (pin "MP1") (pinfunction "MP1_MP1") (pintype "bidirectional"))
      (node (ref "J2-HEADER") (pin "MP2") (pinfunction "MP2_MP2") (pintype "bidirectional"))
      (node (ref "R34") (pin "1") (pinfunction "1_1") (pintype "passive"))
    )
    (net (code "36") (name "IN1A") (class "Default")
      (node (ref "IC10") (pin "21") (pinfunction "SDOUT_21") (pintype "bidirectional"))
      (node (ref "IC5") (pin "21") (pinfunction "SDOUT_21") (pintype "bidirectional"))
      (node (ref "J1-RECEPT") (pin "23") (pinfunction "23_23") (pintype "bidirectional"))
      (node (ref "J1-RECEPT") (pin "24") (pinfunction "24_24") (pintype "bidirectional"))
      (node (ref "J2-HEADER") (pin "27") (pinfunction "27_27") (pintype "bidirectional"))
      (node (ref "J2-HEADER") (pin "28") (pinfunction "28_28") (pintype "bidirectional"))
    )
    (net (code "37") (name "IN1B") (class "Default")
      (node (ref "J1-RECEPT") (pin "27") (pinfunction "27_27") (pintype "bidirectional"))
      (node (ref "J1-RECEPT") (pin "28") (pinfunction "28_28") (pintype "bidirectional"))
      (node (ref "J2-HEADER") (pin "31") (pinfunction "31_31") (pintype "bidirectional"))
      (node (ref "J2-HEADER") (pin "32") (pinfunction "32_32") (pintype "bidirectional"))
    )
    (net (code "38") (name "LRCK") (class "Default")
      (node (ref "IC10") (pin "23") (pinfunction "FSYNC_23") (pintype "bidirectional"))
      (node (ref "IC5") (pin "23") (pinfunction "FSYNC_23") (pintype "bidirectional"))
      (node (ref "J1-RECEPT") (pin "39") (pinfunction "39_39") (pintype "bidirectional"))
      (node (ref "J1-RECEPT") (pin "40") (pinfunction "40_40") (pintype "bidirectional"))
      (node (ref "J2-HEADER") (pin "39") (pinfunction "39_39") (pintype "bidirectional"))
      (node (ref "J2-HEADER") (pin "40") (pinfunction "40_40") (pintype "bidirectional"))
    )
    (net (code "39") (name "MICBIAS") (class "Default")
      (node (ref "IC5") (pin "5") (pinfunction "MICBIAS_5") (pintype "bidirectional"))
      (node (ref "R35") (pin "2") (pinfunction "2_2") (pintype "passive"))
    )
    (net (code "40") (name "Net-(C7-Pad1)") (class "Default")
      (node (ref "C7") (pin "1") (pinfunction "1_1") (pintype "passive"))
      (node (ref "R14") (pin "2") (pinfunction "2_2") (pintype "passive"))
    )
    (net (code "41") (name "Net-(C8-Pad1)") (class "Default")
      (node (ref "C8") (pin "1") (pinfunction "1_1") (pintype "passive"))
      (node (ref "R15") (pin "2") (pinfunction "2_2") (pintype "passive"))
    )
    (net (code "42") (name "Net-(C9-Pad1)") (class "Default")
      (node (ref "C9") (pin "1") (pinfunction "1_1") (pintype "passive"))
      (node (ref "R16") (pin "2") (pinfunction "2_2") (pintype "passive"))
    )
    (net (code "43") (name "Net-(C10-Pad1)") (class "Default")
      (node (ref "C10") (pin "1") (pinfunction "1_1") (pintype "passive"))
      (node (ref "R17") (pin "2") (pinfunction "2_2") (pintype "passive"))
    )
    (net (code "44") (name "Net-(C29-Pad1)") (class "Default")
      (node (ref "C29") (pin "1") (pinfunction "1_1") (pintype "passive"))
      (node (ref "R36") (pin "2") (pinfunction "2_2") (pintype "passive"))
    )
    (net (code "45") (name "Net-(C30-Pad1)") (class "Default")
      (node (ref "C30") (pin "1") (pinfunction "1_1") (pintype "passive"))
      (node (ref "R37") (pin "2") (pinfunction "2_2") (pintype "passive"))
    )
    (net (code "46") (name "Net-(C31-Pad1)") (class "Default")
      (node (ref "C31") (pin "1") (pinfunction "1_1") (pintype "passive"))
      (node (ref "R38") (pin "2") (pinfunction "2_2") (pintype "passive"))
    )
    (net (code "47") (name "Net-(C32-Pad1)") (class "Default")
      (node (ref "C32") (pin "1") (pinfunction "1_1") (pintype "passive"))
      (node (ref "R39") (pin "2") (pinfunction "2_2") (pintype "passive"))
    )
    (net (code "48") (name "Net-(IC3A-+IN)") (class "Default")
      (node (ref "C11") (pin "2") (pinfunction "2_2") (pintype "passive"))
      (node (ref "IC3") (pin "3") (pinfunction "+IN_3") (pintype "input"))
      (node (ref "R18") (pin "1") (pinfunction "1_1") (pintype "passive"))
      (node (ref "R22") (pin "1") (pinfunction "1_1") (pintype "passive"))
    )
    (net (code "49") (name "Net-(IC3A--IN)") (class "Default")
      (node (ref "IC3") (pin "2") (pinfunction "-IN_2") (pintype "input"))
      (node (ref "R26") (pin "2") (pinfunction "2_2") (pintype "passive"))
      (node (ref "R30") (pin "1") (pinfunction "1_1") (pintype "passive"))
    )
    (net (code "50") (name "Net-(IC3B-+IN)") (class "Default")
      (node (ref "C12") (pin "2") (pinfunction "2_2") (pintype "passive"))
      (node (ref "IC3") (pin "5") (pinfunction "+IN_5") (pintype "input"))
      (node (ref "R19") (pin "1") (pinfunction "1_1") (pintype "passive"))
      (node (ref "R23") (pin "1") (pinfunction "1_1") (pintype "passive"))
    )
    (net (code "51") (name "Net-(IC3B--IN)") (class "Default")
      (node (ref "IC3") (pin "6") (pinfunction "-IN_6") (pintype "input"))
      (node (ref "R27") (pin "2") (pinfunction "2_2") (pintype "passive"))
      (node (ref "R31") (pin "1") (pinfunction "1_1") (pintype "passive"))
    )
    (net (code "52") (name "Net-(IC4A-+IN)") (class "Default")
      (node (ref "C13") (pin "2") (pinfunction "2_2") (pintype "passive"))
      (node (ref "IC4") (pin "3") (pinfunction "+IN_3") (pintype "input"))
      (node (ref "R20") (pin "1") (pinfunction "1_1") (pintype "passive"))
      (node (ref "R24") (pin "1") (pinfunction "1_1") (pintype "passive"))
    )
    (net (code "53") (name "Net-(IC4A--IN)") (class "Default")
      (node (ref "IC4") (pin "2") (pinfunction "-IN_2") (pintype "input"))
      (node (ref "R28") (pin "2") (pinfunction "2_2") (pintype "passive"))
      (node (ref "R32") (pin "1") (pinfunction "1_1") (pintype "passive"))
    )
    (net (code "54") (name "Net-(IC4B-+IN)") (class "Default")
      (node (ref "C14") (pin "2") (pinfunction "2_2") (pintype "passive"))
      (node (ref "IC4") (pin "5") (pinfunction "+IN_5") (pintype "input"))
      (node (ref "R21") (pin "1") (pinfunction "1_1") (pintype "passive"))
      (node (ref "R25") (pin "1") (pinfunction "1_1") (pintype "passive"))
    )
    (net (code "55") (name "Net-(IC4B--IN)") (class "Default")
      (node (ref "IC4") (pin "6") (pinfunction "-IN_6") (pintype "input"))
      (node (ref "R29") (pin "2") (pinfunction "2_2") (pintype "passive"))
      (node (ref "R33") (pin "1") (pinfunction "1_1") (pintype "passive"))
    )
    (net (code "56") (name "Net-(IC7A-+IN)") (class "Default")
      (node (ref "C33") (pin "2") (pinfunction "2_2") (pintype "passive"))
      (node (ref "IC7") (pin "3") (pinfunction "+IN_3") (pintype "input"))
      (node (ref "R40") (pin "1") (pinfunction "1_1") (pintype "passive"))
      (node (ref "R44") (pin "1") (pinfunction "1_1") (pintype "passive"))
    )
    (net (code "57") (name "Net-(IC7A--IN)") (class "Default")
      (node (ref "IC7") (pin "2") (pinfunction "-IN_2") (pintype "input"))
      (node (ref "R48") (pin "2") (pinfunction "2_2") (pintype "passive"))
      (node (ref "R53") (pin "1") (pinfunction "1_1") (pintype "passive"))
    )
    (net (code "58") (name "Net-(IC7B-+IN)") (class "Default")
      (node (ref "C34") (pin "2") (pinfunction "2_2") (pintype "passive"))
      (node (ref "IC7") (pin "5") (pinfunction "+IN_5") (pintype "input"))
      (node (ref "R41") (pin "1") (pinfunction "1_1") (pintype "passive"))
      (node (ref "R45") (pin "1") (pinfunction "1_1") (pintype "passive"))
    )
    (net (code "59") (name "Net-(IC7B--IN)") (class "Default")
      (node (ref "IC7") (pin "6") (pinfunction "-IN_6") (pintype "input"))
      (node (ref "R49") (pin "2") (pinfunction "2_2") (pintype "passive"))
      (node (ref "R54") (pin "1") (pinfunction "1_1") (pintype "passive"))
    )
    (net (code "60") (name "Net-(IC8A-+IN)") (class "Default")
      (node (ref "C35") (pin "2") (pinfunction "2_2") (pintype "passive"))
      (node (ref "IC8") (pin "3") (pinfunction "+IN_3") (pintype "input"))
      (node (ref "R42") (pin "1") (pinfunction "1_1") (pintype "passive"))
      (node (ref "R46") (pin "1") (pinfunction "1_1") (pintype "passive"))
    )
    (net (code "61") (name "Net-(IC8A--IN)") (class "Default")
      (node (ref "IC8") (pin "2") (pinfunction "-IN_2") (pintype "input"))
      (node (ref "R50") (pin "2") (pinfunction "2_2") (pintype "passive"))
      (node (ref "R55") (pin "1") (pinfunction "1_1") (pintype "passive"))
    )
    (net (code "62") (name "Net-(IC8B-+IN)") (class "Default")
      (node (ref "C36") (pin "2") (pinfunction "2_2") (pintype "passive"))
      (node (ref "IC8") (pin "5") (pinfunction "+IN_5") (pintype "input"))
      (node (ref "R43") (pin "1") (pinfunction "1_1") (pintype "passive"))
      (node (ref "R47") (pin "1") (pinfunction "1_1") (pintype "passive"))
    )
    (net (code "63") (name "Net-(IC8B--IN)") (class "Default")
      (node (ref "IC8") (pin "6") (pinfunction "-IN_6") (pintype "input"))
      (node (ref "R51") (pin "2") (pinfunction "2_2") (pintype "passive"))
      (node (ref "R56") (pin "1") (pinfunction "1_1") (pintype "passive"))
    )
    (net (code "64") (name "SCL") (class "Default")
      (node (ref "IC10") (pin "17") (pinfunction "SCL_MOSI_17") (pintype "bidirectional"))
      (node (ref "IC5") (pin "17") (pinfunction "SCL_MOSI_17") (pintype "bidirectional"))
      (node (ref "J1-RECEPT") (pin "15") (pinfunction "15_15") (pintype "bidirectional"))
      (node (ref "J1-RECEPT") (pin "16") (pinfunction "16_16") (pintype "bidirectional"))
      (node (ref "J2-HEADER") (pin "15") (pinfunction "15_15") (pintype "bidirectional"))
      (node (ref "J2-HEADER") (pin "16") (pinfunction "16_16") (pintype "bidirectional"))
    )
    (net (code "65") (name "SDA") (class "Default")
      (node (ref "IC10") (pin "18") (pinfunction "SDA_SSZ_18") (pintype "bidirectional"))
      (node (ref "IC5") (pin "18") (pinfunction "SDA_SSZ_18") (pintype "bidirectional"))
      (node (ref "J1-RECEPT") (pin "19") (pinfunction "19_19") (pintype "bidirectional"))
      (node (ref "J1-RECEPT") (pin "20") (pinfunction "20_20") (pintype "bidirectional"))
      (node (ref "J2-HEADER") (pin "19") (pinfunction "19_19") (pintype "bidirectional"))
      (node (ref "J2-HEADER") (pin "20") (pinfunction "20_20") (pintype "bidirectional"))
    )
    (net (code "66") (name "SHDN") (class "Default")
      (node (ref "IC10") (pin "14") (pinfunction "SHDNZ_14") (pintype "bidirectional"))
      (node (ref "IC5") (pin "14") (pinfunction "SHDNZ_14") (pintype "bidirectional"))
      (node (ref "J1-RECEPT") (pin "3") (pinfunction "3_3") (pintype "bidirectional"))
      (node (ref "J1-RECEPT") (pin "4") (pinfunction "4_4") (pintype "bidirectional"))
      (node (ref "J2-HEADER") (pin "3") (pinfunction "3_3") (pintype "bidirectional"))
      (node (ref "J2-HEADER") (pin "4") (pinfunction "4_4") (pintype "bidirectional"))
    )
    (net (code "67") (name "VDD") (class "Default")
      (node (ref "C26") (pin "2") (pinfunction "2_2") (pintype "passive"))
      (node (ref "C28") (pin "2") (pinfunction "2_2") (pintype "passive"))
      (node (ref "C48") (pin "2") (pinfunction "2_2") (pintype "passive"))
      (node (ref "C50") (pin "2") (pinfunction "2_2") (pintype "passive"))
      (node (ref "IC10") (pin "19") (pinfunction "IOVDD_19") (pintype "bidirectional"))
      (node (ref "IC5") (pin "16") (pinfunction "ADDR0_SCLK_16") (pintype "bidirectional"))
      (node (ref "IC5") (pin "19") (pinfunction "IOVDD_19") (pintype "bidirectional"))
      (node (ref "J1-RECEPT") (pin "7") (pinfunction "7_7") (pintype "bidirectional"))
      (node (ref "J1-RECEPT") (pin "8") (pinfunction "8_8") (pintype "bidirectional"))
      (node (ref "J2-HEADER") (pin "7") (pinfunction "7_7") (pintype "bidirectional"))
      (node (ref "J2-HEADER") (pin "8") (pinfunction "8_8") (pintype "bidirectional"))
    )
    (net (code "68") (name "VDDA") (class "Default")
      (node (ref "C17") (pin "1") (pinfunction "1_1") (pintype "passive"))
      (node (ref "C18") (pin "1") (pinfunction "1_1") (pintype "passive"))
      (node (ref "C23") (pin "2") (pinfunction "2_2") (pintype "passive"))
      (node (ref "C24") (pin "2") (pinfunction "2_2") (pintype "passive"))
      (node (ref "C3") (pin "1") (pinfunction "1_1") (pintype "passive"))
      (node (ref "C39") (pin "1") (pinfunction "1_1") (pintype "passive"))
      (node (ref "C40") (pin "1") (pinfunction "1_1") (pintype "passive"))
      (node (ref "C45") (pin "2") (pinfunction "2_2") (pintype "passive"))
      (node (ref "C46") (pin "2") (pinfunction "2_2") (pintype "passive"))
      (node (ref "IC10") (pin "1") (pinfunction "AVDD_1") (pintype "bidirectional"))
      (node (ref "IC2") (pin "5") (pinfunction "OUT_5") (pintype "output"))
      (node (ref "IC3") (pin "8") (pinfunction "V+_8") (pintype "power_in"))
      (node (ref "IC4") (pin "8") (pinfunction "V+_8") (pintype "power_in"))
      (node (ref "IC5") (pin "1") (pinfunction "AVDD_1") (pintype "bidirectional"))
      (node (ref "IC7") (pin "8") (pinfunction "V+_8") (pintype "power_in"))
      (node (ref "IC8") (pin "8") (pinfunction "V+_8") (pintype "power_in"))
    )
    (net (code "69") (name "VGND") (class "Default")
      (node (ref "C15") (pin "1") (pinfunction "1_1") (pintype "passive"))
      (node (ref "C16") (pin "1") (pinfunction "1_1") (pintype "passive"))
      (node (ref "C19") (pin "2") (pinfunction "2_2") (pintype "passive"))
      (node (ref "C37") (pin "1") (pinfunction "1_1") (pintype "passive"))
      (node (ref "C38") (pin "1") (pinfunction "1_1") (pintype "passive"))
      (node (ref "R1") (pin "2") (pinfunction "2_2") (pintype "passive"))
      (node (ref "R22") (pin "2") (pinfunction "2_2") (pintype "passive"))
      (node (ref "R23") (pin "2") (pinfunction "2_2") (pintype "passive"))
      (node (ref "R24") (pin "2") (pinfunction "2_2") (pintype "passive"))
      (node (ref "R25") (pin "2") (pinfunction "2_2") (pintype "passive"))
      (node (ref "R26") (pin "1") (pinfunction "1_1") (pintype "passive"))
      (node (ref "R27") (pin "1") (pinfunction "1_1") (pintype "passive"))
      (node (ref "R28") (pin "1") (pinfunction "1_1") (pintype "passive"))
      (node (ref "R29") (pin "1") (pinfunction "1_1") (pintype "passive"))
      (node (ref "R34") (pin "2") (pinfunction "2_2") (pintype "passive"))
      (node (ref "R35") (pin "1") (pinfunction "1_1") (pintype "passive"))
      (node (ref "R44") (pin "2") (pinfunction "2_2") (pintype "passive"))
      (node (ref "R45") (pin "2") (pinfunction "2_2") (pintype "passive"))
      (node (ref "R46") (pin "2") (pinfunction "2_2") (pintype "passive"))
      (node (ref "R47") (pin "2") (pinfunction "2_2") (pintype "passive"))
      (node (ref "R48") (pin "1") (pinfunction "1_1") (pintype "passive"))
      (node (ref "R49") (pin "1") (pinfunction "1_1") (pintype "passive"))
      (node (ref "R50") (pin "1") (pinfunction "1_1") (pintype "passive"))
      (node (ref "R51") (pin "1") (pinfunction "1_1") (pintype "passive"))
    )
    (net (code "70") (name "VGND1") (class "Default")
      (node (ref "J1-RECEPT") (pin "53") (pinfunction "53_53") (pintype "bidirectional"))
      (node (ref "J2-HEADER") (pin "54") (pinfunction "54_54") (pintype "bidirectional"))
      (node (ref "R1") (pin "1") (pinfunction "1_1") (pintype "passive"))
    )
    (net (code "71") (name "VREF-A") (class "Default")
      (node (ref "C20") (pin "2") (pinfunction "2_2") (pintype "passive"))
      (node (ref "IC5") (pin "3") (pinfunction "VREF_3") (pintype "bidirectional"))
    )
    (net (code "72") (name "VREF-B") (class "Default")
      (node (ref "C42") (pin "2") (pinfunction "2_2") (pintype "passive"))
      (node (ref "IC10") (pin "3") (pinfunction "VREF_3") (pintype "bidirectional"))
    )
    (net (code "73") (name "unconnected-(IC5-GPIO1-Pad20)") (class "Default")
      (node (ref "IC5") (pin "20") (pinfunction "GPIO1_20") (pintype "bidirectional"))
    )
    (net (code "74") (name "unconnected-(IC10-GPIO1-Pad20)") (class "Default")
      (node (ref "IC10") (pin "20") (pinfunction "GPIO1_20") (pintype "bidirectional"))
    )
    (net (code "75") (name "unconnected-(IC10-MICBIAS-Pad5)") (class "Default")
      (node (ref "IC10") (pin "5") (pinfunction "MICBIAS_5") (pintype "bidirectional"))
    )
    (net (code "76") (name "unconnected-(J1-RECEPT-Pad31)") (class "Default")
      (node (ref "J1-RECEPT") (pin "31") (pinfunction "31_31") (pintype "bidirectional"))
    )
    (net (code "77") (name "unconnected-(J1-RECEPT-Pad32)") (class "Default")
      (node (ref "J1-RECEPT") (pin "32") (pinfunction "32_32") (pintype "bidirectional"))
    )
    (net (code "78") (name "unconnected-(J1-RECEPT-Pad50)") (class "Default")
      (node (ref "J1-RECEPT") (pin "50") (pinfunction "50_50") (pintype "bidirectional"))
    )
    (net (code "79") (name "unconnected-(J1-RECEPT-Pad54)") (class "Default")
      (node (ref "J1-RECEPT") (pin "54") (pinfunction "54_54") (pintype "bidirectional"))
    )
    (net (code "80") (name "unconnected-(J1-RECEPT-Pad58)") (class "Default")
      (node (ref "J1-RECEPT") (pin "58") (pinfunction "58_58") (pintype "bidirectional"))
    )
    (net (code "81") (name "unconnected-(J2-HEADER-Pad23)") (class "Default")
      (node (ref "J2-HEADER") (pin "23") (pinfunction "23_23") (pintype "bidirectional"))
    )
    (net (code "82") (name "unconnected-(J2-HEADER-Pad24)") (class "Default")
      (node (ref "J2-HEADER") (pin "24") (pinfunction "24_24") (pintype "bidirectional"))
    )
    (net (code "83") (name "unconnected-(J2-HEADER-Pad49)") (class "Default")
      (node (ref "J2-HEADER") (pin "49") (pinfunction "49_49") (pintype "bidirectional"))
    )
    (net (code "84") (name "unconnected-(J2-HEADER-Pad53)") (class "Default")
      (node (ref "J2-HEADER") (pin "53") (pinfunction "53_53") (pintype "bidirectional"))
    )
    (net (code "85") (name "unconnected-(J2-HEADER-Pad57)") (class "Default")
      (node (ref "J2-HEADER") (pin "57") (pinfunction "57_57") (pintype "bidirectional"))
    )
  )
)
